# ArduinoCustomSchematic.net
KiCad netlist of a schematic drawn in Altium Designer
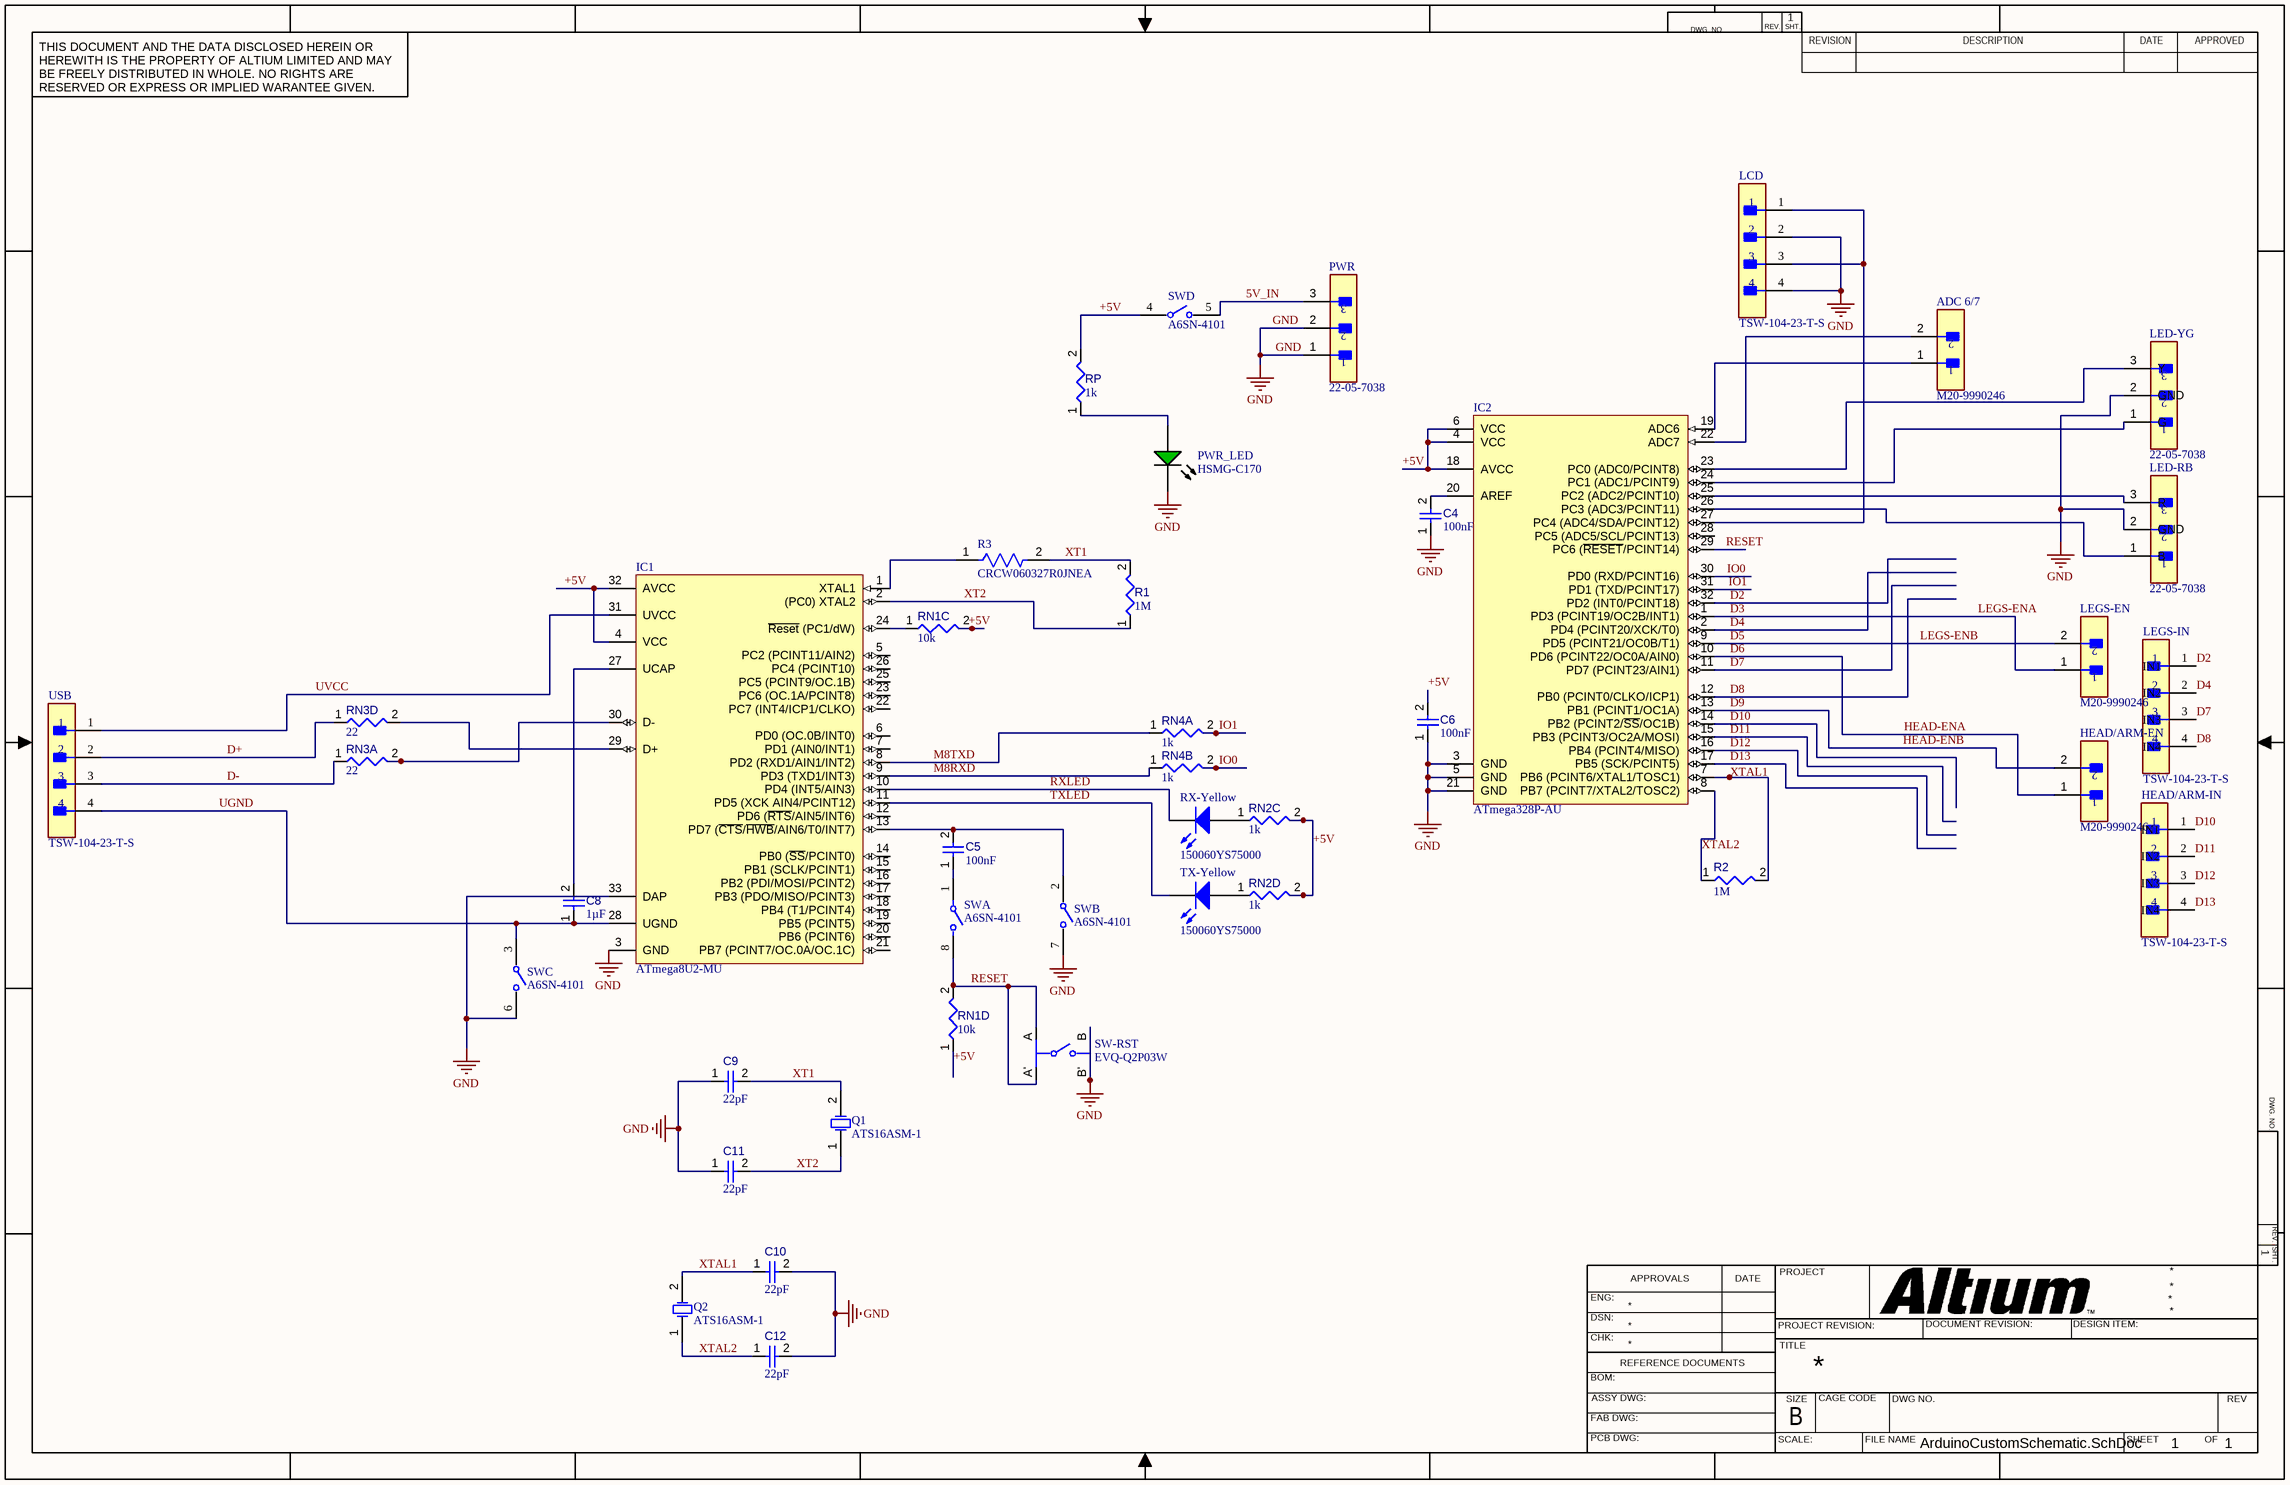
[diagram p0: ArduinoCustomSchematic.SchDoc]

(export (version "E")
  (design (tool "Eeschema 10.0.6"))
  (components
    (comp (ref "ADC 6/7")
      (value "M20-9990246")
      (footprint "FP-M20-9990246-MFG")
      (description "CONN HEADER VERT 2POS 2.54MM")
      (fields
        (field (name "OCTOPART") "https://octopart.com/m20-9990246-harwin-2590635")
        (field (name "MANUFACTURER") "Harwin")
      )
      (libsource (lib "Altium Content Vault") (part "3bc925449376181038e59eaffc5286c"))
    )
    (comp (ref "C4")
      (value "100nF")
      (footprint "CAPC2013X95X50LL10T25")
      (description "Chip Capacitor, 100 nF, +/- 10%, 50 V, 0805 (2012 Metric)")
      (fields (field (name "TOLERANCE") "10%") (field (name "Comment") "Capacitor 100 nF +/-10% 50 V 0805"))
      (libsource (lib "MY-PC-ER") (part "CAP-NP-2"))
    )
    (comp (ref "C5")
      (value "100nF")
      (footprint "CAPC2013X95X50LL10T25")
      (description "Chip Capacitor, 100 nF, +/- 10%, 50 V, 0805 (2012 Metric)")
      (fields (field (name "TOLERANCE") "10%") (field (name "Comment") "Capacitor 100 nF +/-10% 50 V 0805"))
      (libsource (lib "MY-PC-ER") (part "CAP-NP-2"))
    )
    (comp (ref "C6")
      (value "100nF")
      (footprint "CAPC2013X95X50LL10T25")
      (description "Chip Capacitor, 100 nF, +/- 10%, 50 V, 0805 (2012 Metric)")
      (fields (field (name "TOLERANCE") "10%") (field (name "Comment") "Capacitor 100 nF +/-10% 50 V 0805"))
      (libsource (lib "MY-PC-ER") (part "CAP-NP-2"))
    )
    (comp (ref "C8")
      (value "1µF")
      (footprint "CAPC1608X90X35ML15T15")
      (description "Chip Capacitor, 1 uF, +/- 10%, 16 V, 0603 (1608 Metric)")
      (fields (field (name "TOLERANCE") "10%") (field (name "Comment") "Capacitor 1uF +/- 10% 16V 0603"))
      (libsource (lib "MY-PC-ER") (part "CAP-NP-2"))
    )
    (comp (ref "C9")
      (value "22pF")
      (footprint "CAPC0402(1005)60_L")
      (description "Chip Capacitor, 22pF +/-10%, 50V, 0402, Thickness 0.6 mm")
      (fields (field (name "TOLERANCE") "10%") (field (name "Comment") "Capacitor 22pF +/-10% 50V 0402"))
      (libsource (lib "MY-PC-ER") (part "CAP-NP-2"))
    )
    (comp (ref "C10")
      (value "22pF")
      (footprint "CAPC0402(1005)60_L")
      (description "Chip Capacitor, 22pF +/-10%, 50V, 0402, Thickness 0.6 mm")
      (fields (field (name "TOLERANCE") "10%") (field (name "Comment") "Capacitor 22pF +/-10% 50V 0402"))
      (libsource (lib "MY-PC-ER") (part "CAP-NP-2"))
    )
    (comp (ref "C11")
      (value "22pF")
      (footprint "CAPC0402(1005)60_L")
      (description "Chip Capacitor, 22pF +/-10%, 50V, 0402, Thickness 0.6 mm")
      (fields (field (name "TOLERANCE") "10%") (field (name "Comment") "Capacitor 22pF +/-10% 50V 0402"))
      (libsource (lib "MY-PC-ER") (part "CAP-NP-2"))
    )
    (comp (ref "C12")
      (value "22pF")
      (footprint "CAPC0402(1005)60_L")
      (description "Chip Capacitor, 22pF +/-10%, 50V, 0402, Thickness 0.6 mm")
      (fields (field (name "TOLERANCE") "10%") (field (name "Comment") "Capacitor 22pF +/-10% 50V 0402"))
      (libsource (lib "MY-PC-ER") (part "CAP-NP-2"))
    )
    (comp (ref "HEAD/ARM-EN")
      (value "M20-9990246")
      (footprint "FP-M20-9990246-MFG")
      (description "CONN HEADER VERT 2POS 2.54MM")
      (fields
        (field (name "OCTOPART") "https://octopart.com/m20-9990246-harwin-2590635")
        (field (name "MANUFACTURER") "Harwin")
      )
      (libsource (lib "Altium Content Vault") (part "3bc925449376181038e59eaffc5286c"))
    )
    (comp (ref "HEAD/ARM-IN")
      (value "TSW-104-23-T-S")
      (footprint "FP-TSW-104-23-T-S-MFG")
      (description "CONN HEADER VERT 4POS 2.54MM")
      (libsource (lib "Altium Content Vault") (part "f33e0d423099bbb9e64512431cdbdf7"))
    )
    (comp (ref "IC1")
      (value "ATmega8U2-MU")
      (footprint "32PG_M")
      (libsource (lib "Altium Content Vault") (part "MC-8B-ATM8U2-SQ33"))
    )
    (comp (ref "IC2")
      (value "ATmega328P-AU")
      (footprint "32A_M")
      (libsource (lib "Altium Content Vault") (part "MC-8B-ATM48-SQ32"))
    )
    (comp (ref "LCD")
      (value "TSW-104-23-T-S")
      (footprint "FP-TSW-104-23-T-S-MFG")
      (description "CONN HEADER VERT 4POS 2.54MM")
      (libsource (lib "") (part "f33e0d423099bbb9e64512431cdbdf7_1"))
    )
    (comp (ref "LED-RB")
      (value "22-05-7038")
      (footprint "FP-22-05-7038-MFG")
      (description "CONN HEADER R/A 3POS 2.54MM")
      (fields
        (field (name "OCTOPART") "https://octopart.com/22-05-7038-molex-773563")
        (field (name "MANUFACTURER") "Molex")
      )
      (libsource (lib "") (part "0d3f023dd272f625e17a2be33dea85f_1"))
    )
    (comp (ref "LED-YG")
      (value "22-05-7038")
      (footprint "FP-22-05-7038-MFG")
      (description "CONN HEADER R/A 3POS 2.54MM")
      (fields
        (field (name "OCTOPART") "https://octopart.com/22-05-7038-molex-773563")
        (field (name "MANUFACTURER") "Molex")
      )
      (libsource (lib "") (part "0d3f023dd272f625e17a2be33dea85f_2"))
    )
    (comp (ref "LEGS-EN")
      (value "M20-9990246")
      (footprint "FP-M20-9990246-MFG")
      (description "CONN HEADER VERT 2POS 2.54MM")
      (fields
        (field (name "OCTOPART") "https://octopart.com/m20-9990246-harwin-2590635")
        (field (name "MANUFACTURER") "Harwin")
      )
      (libsource (lib "Altium Content Vault") (part "3bc925449376181038e59eaffc5286c"))
    )
    (comp (ref "LEGS-IN")
      (value "TSW-104-23-T-S")
      (footprint "FP-TSW-104-23-T-S-MFG")
      (description "CONN HEADER VERT 4POS 2.54MM")
      (libsource (lib "Altium Content Vault") (part "f33e0d423099bbb9e64512431cdbdf7"))
    )
    (comp (ref "PWR")
      (value "22-05-7038")
      (footprint "FP-22-05-7038-MFG")
      (description "CONN HEADER R/A 3POS 2.54MM")
      (fields
        (field (name "OCTOPART") "https://octopart.com/22-05-7038-molex-773563")
        (field (name "MANUFACTURER") "Molex")
      )
      (libsource (lib "Altium Content Vault") (part "0d3f023dd272f625e17a2be33dea85f"))
    )
    (comp (ref "PWR_LED")
      (value "HSMG-C170")
      (footprint "AVAG-HSMX-C170_V")
      (description "Chip LED, Green, 2.2 V, -40 to 85 degC, 2-Pin SMD, Pb-Free, Tape and Reel")
      (fields (field (name "MANUFACTURER") "Avago"))
      (libsource (lib "Altium Content Vault") (part "LED_GREEN_A1K2-2"))
    )
    (comp (ref "Q1")
      (value "ATS16ASM-1")
      (footprint "CTS-ATS-SM-XTAL-2")
      (description "ATS-SM Series Quartz Crystal, 16 MHz, -20 to 70 degC, 11.1 x 4.83 x 4.3mm SMD, RoHS, Tape and Reel")
      (fields (field (name "MANUFACTURER") "CTS Corporation"))
      (libsource (lib "Altium Content Vault") (part "CTS-ATS-SM-XTAL-2"))
    )
    (comp (ref "Q2")
      (value "ATS16ASM-1")
      (footprint "CTS-ATS-SM-XTAL-2")
      (description "ATS-SM Series Quartz Crystal, 16 MHz, -20 to 70 degC, 11.1 x 4.83 x 4.3mm SMD, RoHS, Tape and Reel")
      (fields (field (name "MANUFACTURER") "CTS Corporation"))
      (libsource (lib "Altium Content Vault") (part "CTS-ATS-SM-XTAL-2"))
    )
    (comp (ref "R1")
      (value "1M")
      (footprint "RESC0402(1005)_L")
      (description "Chip Resistor, 1 MOhms, +/-5 %, 63 mW, -55 to 155 degC, 0402")
      (fields (field (name "POWER") "63mW") (field (name "TOLERANCE") "5%"))
      (libsource (lib "MY-PC-ER") (part "RES-2"))
    )
    (comp (ref "R2")
      (value "1M")
      (footprint "RESC0402(1005)_L")
      (description "Chip Resistor, 1 MOhms, +/-5 %, 63 mW, -55 to 155 degC, 0402")
      (fields (field (name "POWER") "63mW") (field (name "TOLERANCE") "5%"))
      (libsource (lib "MY-PC-ER") (part "RES-2"))
    )
    (comp (ref "R3")
      (value "CRCW060327R0JNEA")
      (footprint "FP-CRCW0603-e3-IPC_B")
      (description "RES Thick Film, 27Ω, 5%, 0.1W, 200ppm/°C, 0603")
      (fields (field (name "TOLERANCE") "5%"))
      (libsource (lib "Altium Content Vault") (part "1029c3af85768c4190bb7ad29bc67b5"))
    )
    (comp (ref "RN1C")
      (value "10k")
      (footprint "RESC0402(1005)_L")
      (description "Chip Resistor, 10 kOhms, +/-1 %, 63 mW, -55 to 125 degC, 0402")
      (fields (field (name "POWER") "63mW") (field (name "TOLERANCE") "1%"))
      (libsource (lib "MY-PC-ER") (part "RES-2"))
    )
    (comp (ref "RN1D")
      (value "10k")
      (footprint "RESC0402(1005)_L")
      (description "Chip Resistor, 10 kOhms, +/-1 %, 63 mW, -55 to 125 degC, 0402")
      (fields (field (name "POWER") "63mW") (field (name "TOLERANCE") "1%"))
      (libsource (lib "MY-PC-ER") (part "RES-2"))
    )
    (comp (ref "RN2C")
      (value "1k")
      (footprint "RESC0402(1005)_L")
      (description "Chip Resistor, 1 kOhms, +/-5 %, 63 mW, -55 to 155 degC, 0402")
      (fields (field (name "POWER") "63mW") (field (name "TOLERANCE") "5%"))
      (libsource (lib "MY-PC-ER") (part "RES-2"))
    )
    (comp (ref "RN2D")
      (value "1k")
      (footprint "RESC0402(1005)_L")
      (description "Chip Resistor, 1 kOhms, +/-5 %, 63 mW, -55 to 155 degC, 0402")
      (fields (field (name "POWER") "63mW") (field (name "TOLERANCE") "5%"))
      (libsource (lib "MY-PC-ER") (part "RES-2"))
    )
    (comp (ref "RN3A")
      (value "22")
      (footprint "RESC0402(1005)_L")
      (description "Chip Resistor, 22 Ohms, +/-5 %, 63 mW, -55 to 155 degC, 0402")
      (fields (field (name "TOLERANCE") "5%") (field (name "POWER") "63mW"))
      (libsource (lib "MY-PC-ER") (part "RES-2"))
    )
    (comp (ref "RN3D")
      (value "22")
      (footprint "RESC0402(1005)_L")
      (description "Chip Resistor, 22 Ohms, +/-5 %, 63 mW, -55 to 155 degC, 0402")
      (fields (field (name "TOLERANCE") "5%") (field (name "POWER") "63mW"))
      (libsource (lib "MY-PC-ER") (part "RES-2"))
    )
    (comp (ref "RN4A")
      (value "1k")
      (footprint "RESC0402(1005)_L")
      (description "Chip Resistor, 1 kOhms, +/-5 %, 63 mW, -55 to 155 degC, 0402")
      (fields (field (name "POWER") "63mW") (field (name "TOLERANCE") "5%"))
      (libsource (lib "MY-PC-ER") (part "RES-2"))
    )
    (comp (ref "RN4B")
      (value "1k")
      (footprint "RESC0402(1005)_L")
      (description "Chip Resistor, 1 kOhms, +/-5 %, 63 mW, -55 to 155 degC, 0402")
      (fields (field (name "POWER") "63mW") (field (name "TOLERANCE") "5%"))
      (libsource (lib "MY-PC-ER") (part "RES-2"))
    )
    (comp (ref "RP")
      (value "1k")
      (footprint "RESC0805(2012)_L")
      (description "Chip Resistor, 1 kOhms, +/-5%, 125 mW, -55 to 155 degC, 0805")
      (fields (field (name "TOLERANCE") "5%") (field (name "POWER") "125mW"))
      (libsource (lib "MY-PC-ER") (part "RES-2"))
    )
    (comp (ref "RX-Yellow")
      (value "150060YS75000")
      (footprint "0603_A")
      (description "SMD mono-color Chip LED, WL-SMCW, Yellow")
      (fields (field (name "MANUFACTURER") "Wuerth Elektronik"))
      (libsource (lib "Altium Content Vault") (part "WE-LED_K1A2-2"))
    )
    (comp (ref "SW")
      (value "A6SN-4101")
      (footprint "FP-A6SN-4101-MFG")
      (description "RESET-EN")
      (libsource (lib "Altium Content Vault") (part "3efd76fef6de25c549b18e73c4a40b0"))
    )
    (comp (ref "SW-RST")
      (value "EVQ-Q2P03W")
      (footprint "FP-EVQ-Q2P03W-MFG")
      (description "SWITCH TACTILE SPST-NO 0.02A 15V")
      (libsource (lib "Altium Content Vault") (part "9677229990528492022b31d4503349f"))
    )
    (comp (ref "TX-Yellow")
      (value "150060YS75000")
      (footprint "0603_A")
      (description "SMD mono-color Chip LED, WL-SMCW, Yellow")
      (fields (field (name "MANUFACTURER") "Wuerth Elektronik"))
      (libsource (lib "Altium Content Vault") (part "WE-LED_K1A2-2"))
    )
    (comp (ref "USB")
      (value "TSW-104-23-T-S")
      (footprint "FP-TSW-104-23-T-S-MFG")
      (description "CONN HEADER VERT 4POS 2.54MM")
      (libsource (lib "") (part "f33e0d423099bbb9e64512431cdbdf7_1"))
    )
  )
  (nets
    (net (code "1") (name "/+5V") (class "Default")
      (node (ref "C6") (pin "2") (pinfunction "2_2") (pintype "passive"))
      (node (ref "IC1") (pin "32") (pinfunction "AVCC_32") (pintype "power_in"))
      (node (ref "IC1") (pin "4") (pinfunction "VCC_4") (pintype "power_in"))
      (node (ref "IC2") (pin "18") (pinfunction "AVCC_18") (pintype "power_in"))
      (node (ref "IC2") (pin "4") (pinfunction "VCC_4") (pintype "power_in"))
      (node (ref "IC2") (pin "6") (pinfunction "VCC_6") (pintype "power_in"))
      (node (ref "RN1C") (pin "2") (pinfunction "2_2") (pintype "passive"))
      (node (ref "RN1D") (pin "1") (pinfunction "1_1") (pintype "passive"))
      (node (ref "RN2C") (pin "2") (pinfunction "2_2") (pintype "passive"))
      (node (ref "RN2D") (pin "2") (pinfunction "2_2") (pintype "passive"))
      (node (ref "RP") (pin "2") (pinfunction "2_2") (pintype "passive"))
      (node (ref "SW") (pin "4") (pinfunction "4_4") (pintype "passive"))
    )
    (net (code "2") (name "/5V_IN") (class "Default")
      (node (ref "PWR") (pin "3") (pinfunction "3_3") (pintype "passive"))
      (node (ref "SW") (pin "5") (pinfunction "5_5") (pintype "passive"))
    )
    (net (code "3") (name "/D+") (class "Default")
      (node (ref "RN3D") (pin "1") (pinfunction "1_1") (pintype "passive"))
      (node (ref "USB") (pin "2") (pinfunction "D+_2") (pintype "passive"))
    )
    (net (code "4") (name "/D-") (class "Default")
      (node (ref "RN3A") (pin "1") (pinfunction "1_1") (pintype "passive"))
      (node (ref "USB") (pin "3") (pinfunction "D-_3") (pintype "passive"))
    )
    (net (code "5") (name "/D2") (class "Default")
      (node (ref "IC2") (pin "32") (pinfunction "PD2_(INT0/PCINT18)_32") (pintype "bidirectional"))
      (node (ref "LEGS-IN") (pin "1") (pinfunction "IN1_1") (pintype "passive"))
    )
    (net (code "6") (name "/D3") (class "Default")
      (node (ref "IC2") (pin "1") (pinfunction "PD3_(PCINT19/OC2B/INT1)_1") (pintype "bidirectional"))
      (node (ref "LEGS-EN") (pin "1") (pinfunction "1_1") (pintype "passive"))
    )
    (net (code "7") (name "/D4") (class "Default")
      (node (ref "IC2") (pin "2") (pinfunction "PD4_(PCINT20/XCK/T0)_2") (pintype "bidirectional"))
      (node (ref "LEGS-IN") (pin "2") (pinfunction "IN2_2") (pintype "passive"))
    )
    (net (code "8") (name "/D5") (class "Default")
      (node (ref "IC2") (pin "9") (pinfunction "PD5_(PCINT21/OC0B/T1)_9") (pintype "bidirectional"))
      (node (ref "LEGS-EN") (pin "2") (pinfunction "2_2") (pintype "passive"))
    )
    (net (code "9") (name "/D6") (class "Default")
      (node (ref "HEAD/ARM-EN") (pin "1") (pinfunction "1_1") (pintype "passive"))
      (node (ref "IC2") (pin "10") (pinfunction "PD6_(PCINT22/OC0A/AIN0)_10") (pintype "bidirectional"))
    )
    (net (code "10") (name "/D7") (class "Default")
      (node (ref "IC2") (pin "11") (pinfunction "PD7_(PCINT23/AIN1)_11") (pintype "bidirectional"))
      (node (ref "LEGS-IN") (pin "3") (pinfunction "IN3_3") (pintype "passive"))
    )
    (net (code "11") (name "/D8") (class "Default")
      (node (ref "IC2") (pin "12") (pinfunction "PB0_(PCINT0/CLKO/ICP1)_12") (pintype "bidirectional"))
      (node (ref "LEGS-IN") (pin "4") (pinfunction "IN4_4") (pintype "passive"))
    )
    (net (code "12") (name "/D9") (class "Default")
      (node (ref "HEAD/ARM-EN") (pin "2") (pinfunction "2_2") (pintype "passive"))
      (node (ref "IC2") (pin "13") (pinfunction "PB1_(PCINT1/OC1A)_13") (pintype "bidirectional"))
    )
    (net (code "13") (name "/D10") (class "Default")
      (node (ref "HEAD/ARM-IN") (pin "1") (pinfunction "IN1_1") (pintype "passive"))
      (node (ref "IC2") (pin "14") (pinfunction "PB2_(PCINT2/~{SS}/OC1B)_14") (pintype "bidirectional"))
    )
    (net (code "14") (name "/D11") (class "Default")
      (node (ref "HEAD/ARM-IN") (pin "2") (pinfunction "IN2_2") (pintype "passive"))
      (node (ref "IC2") (pin "15") (pinfunction "PB3_(PCINT3/OC2A/MOSI)_15") (pintype "bidirectional"))
    )
    (net (code "15") (name "/D12") (class "Default")
      (node (ref "HEAD/ARM-IN") (pin "3") (pinfunction "IN3_3") (pintype "passive"))
      (node (ref "IC2") (pin "16") (pinfunction "PB4_(PCINT4/MISO)_16") (pintype "bidirectional"))
    )
    (net (code "16") (name "/D13") (class "Default")
      (node (ref "HEAD/ARM-IN") (pin "4") (pinfunction "IN4_4") (pintype "passive"))
      (node (ref "IC2") (pin "17") (pinfunction "PB5_(SCK/PCINT5)_17") (pintype "bidirectional"))
    )
    (net (code "17") (name "/IO0") (class "Default")
      (node (ref "IC2") (pin "30") (pinfunction "PD0_(RXD/PCINT16)_30") (pintype "bidirectional"))
      (node (ref "RN4B") (pin "2") (pinfunction "2_2") (pintype "passive"))
    )
    (net (code "18") (name "/IO1") (class "Default")
      (node (ref "IC2") (pin "31") (pinfunction "PD1_(TXD/PCINT17)_31") (pintype "bidirectional"))
      (node (ref "RN4A") (pin "2") (pinfunction "2_2") (pintype "passive"))
    )
    (net (code "19") (name "/M8RXD") (class "Default")
      (node (ref "IC1") (pin "9") (pinfunction "PD3_(TXD1/INT3)_9") (pintype "bidirectional"))
      (node (ref "RN4B") (pin "1") (pinfunction "1_1") (pintype "passive"))
    )
    (net (code "20") (name "/M8TXD") (class "Default")
      (node (ref "IC1") (pin "8") (pinfunction "PD2_(RXD1/AIN1/INT2)_8") (pintype "bidirectional"))
      (node (ref "RN4A") (pin "1") (pinfunction "1_1") (pintype "passive"))
    )
    (net (code "21") (name "/RESET") (class "Default")
      (node (ref "IC2") (pin "29") (pinfunction "PC6_(~{RESET}/PCINT14)_29") (pintype "bidirectional"))
      (node (ref "RN1D") (pin "2") (pinfunction "2_2") (pintype "passive"))
      (node (ref "SW") (pin "8") (pinfunction "8_8") (pintype "passive"))
      (node (ref "SW-RST") (pin "A") (pinfunction "A_A") (pintype "passive"))
      (node (ref "SW-RST") (pin "A'") (pinfunction "A'_A'") (pintype "passive"))
    )
    (net (code "22") (name "/RXLED") (class "Default")
      (node (ref "IC1") (pin "10") (pinfunction "PD4_(INT5/AIN3)_10") (pintype "bidirectional"))
      (node (ref "RX-Yellow") (pin "1") (pinfunction "K_1") (pintype "passive"))
    )
    (net (code "23") (name "/TXLED") (class "Default")
      (node (ref "IC1") (pin "11") (pinfunction "PD5_(XCK_AIN4/PCINT12)_11") (pintype "bidirectional"))
      (node (ref "TX-Yellow") (pin "1") (pinfunction "K_1") (pintype "passive"))
    )
    (net (code "24") (name "/UGND") (class "Default")
      (node (ref "C8") (pin "1") (pinfunction "1_1") (pintype "passive"))
      (node (ref "IC1") (pin "28") (pinfunction "UGND_28") (pintype "power_in"))
      (node (ref "SW") (pin "3") (pinfunction "3_3") (pintype "passive"))
      (node (ref "USB") (pin "4") (pinfunction "GND_4") (pintype "passive"))
    )
    (net (code "25") (name "/UVCC") (class "Default")
      (node (ref "IC1") (pin "31") (pinfunction "UVCC_31") (pintype "power_in"))
      (node (ref "USB") (pin "1") (pinfunction "UVCC_1") (pintype "passive"))
    )
    (net (code "26") (name "/XT1") (class "Default")
      (node (ref "C9") (pin "2") (pinfunction "2_2") (pintype "passive"))
      (node (ref "Q1") (pin "2") (pinfunction "X2_2") (pintype "passive"))
      (node (ref "R1") (pin "2") (pinfunction "2_2") (pintype "passive"))
      (node (ref "R3") (pin "2") (pinfunction "2_2") (pintype "passive"))
    )
    (net (code "27") (name "/XT2") (class "Default")
      (node (ref "C11") (pin "2") (pinfunction "2_2") (pintype "passive"))
      (node (ref "IC1") (pin "2") (pinfunction "(PC0)_XTAL2_2") (pintype "bidirectional"))
      (node (ref "Q1") (pin "1") (pinfunction "X1_1") (pintype "passive"))
      (node (ref "R1") (pin "1") (pinfunction "1_1") (pintype "passive"))
    )
    (net (code "28") (name "/XTAL1") (class "Default")
      (node (ref "C10") (pin "1") (pinfunction "1_1") (pintype "passive"))
      (node (ref "IC2") (pin "7") (pinfunction "PB6_(PCINT6/XTAL1/TOSC1)_7") (pintype "bidirectional"))
      (node (ref "Q2") (pin "2") (pinfunction "X2_2") (pintype "passive"))
      (node (ref "R2") (pin "2") (pinfunction "2_2") (pintype "passive"))
    )
    (net (code "29") (name "/XTAL2") (class "Default")
      (node (ref "C12") (pin "1") (pinfunction "1_1") (pintype "passive"))
      (node (ref "IC2") (pin "8") (pinfunction "PB7_(PCINT7/XTAL2/TOSC2)_8") (pintype "bidirectional"))
      (node (ref "Q2") (pin "1") (pinfunction "X1_1") (pintype "passive"))
      (node (ref "R2") (pin "1") (pinfunction "1_1") (pintype "passive"))
    )
    (net (code "30") (name "GND") (class "Default")
      (node (ref "C10") (pin "2") (pinfunction "2_2") (pintype "passive"))
      (node (ref "C11") (pin "1") (pinfunction "1_1") (pintype "passive"))
      (node (ref "C12") (pin "2") (pinfunction "2_2") (pintype "passive"))
      (node (ref "C4") (pin "1") (pinfunction "1_1") (pintype "passive"))
      (node (ref "C6") (pin "1") (pinfunction "1_1") (pintype "passive"))
      (node (ref "C9") (pin "1") (pinfunction "1_1") (pintype "passive"))
      (node (ref "IC1") (pin "3") (pinfunction "GND_3") (pintype "power_in"))
      (node (ref "IC1") (pin "33") (pinfunction "DAP_33") (pintype "power_in"))
      (node (ref "IC2") (pin "21") (pinfunction "GND_21") (pintype "power_in"))
      (node (ref "IC2") (pin "3") (pinfunction "GND_3") (pintype "power_in"))
      (node (ref "IC2") (pin "5") (pinfunction "GND_5") (pintype "power_in"))
      (node (ref "LCD") (pin "2") (pinfunction "D+_2") (pintype "passive"))
      (node (ref "LCD") (pin "4") (pinfunction "GND_4") (pintype "passive"))
      (node (ref "LED-RB") (pin "2") (pinfunction "GND_2") (pintype "passive"))
      (node (ref "LED-YG") (pin "2") (pinfunction "GND_2") (pintype "passive"))
      (node (ref "PWR") (pin "1") (pinfunction "1_1") (pintype "passive"))
      (node (ref "PWR") (pin "2") (pinfunction "2_2") (pintype "passive"))
      (node (ref "PWR_LED") (pin "2") (pinfunction "K_2") (pintype "passive"))
      (node (ref "SW") (pin "6") (pinfunction "6_6") (pintype "passive"))
      (node (ref "SW") (pin "7") (pinfunction "7_7") (pintype "passive"))
      (node (ref "SW-RST") (pin "B") (pinfunction "B_B") (pintype "passive"))
      (node (ref "SW-RST") (pin "B'") (pinfunction "B'_B'") (pintype "passive"))
    )
    (net (code "31") (name "Net-(C5-Pad1)") (class "Default")
      (node (ref "C5") (pin "1") (pinfunction "1_1") (pintype "passive"))
      (node (ref "SW") (pin "1") (pinfunction "1_1") (pintype "passive"))
    )
    (net (code "32") (name "Net-(IC1-D+)") (class "Default")
      (node (ref "IC1") (pin "29") (pinfunction "D+_29") (pintype "bidirectional"))
      (node (ref "RN3D") (pin "2") (pinfunction "2_2") (pintype "passive"))
    )
    (net (code "33") (name "Net-(IC1-D-)") (class "Default")
      (node (ref "IC1") (pin "30") (pinfunction "D-_30") (pintype "bidirectional"))
      (node (ref "RN3A") (pin "2") (pinfunction "2_2") (pintype "passive"))
    )
    (net (code "34") (name "Net-(IC1-PD7_(~{CTS}{slash}~{HWB}{slash}AIN6{slash}T0{slash}INT7))") (class "Default")
      (node (ref "C5") (pin "2") (pinfunction "2_2") (pintype "passive"))
      (node (ref "IC1") (pin "13") (pinfunction "PD7_(~{CTS}/~{HWB}/AIN6/T0/INT7)_13") (pintype "bidirectional"))
      (node (ref "SW") (pin "2") (pinfunction "2_2") (pintype "passive"))
    )
    (net (code "35") (name "Net-(IC1-UCAP)") (class "Default")
      (node (ref "C8") (pin "2") (pinfunction "2_2") (pintype "passive"))
      (node (ref "IC1") (pin "27") (pinfunction "UCAP_27") (pintype "power_in"))
    )
    (net (code "36") (name "Net-(IC1-XTAL1)") (class "Default")
      (node (ref "IC1") (pin "1") (pinfunction "XTAL1_1") (pintype "input"))
      (node (ref "R3") (pin "1") (pinfunction "1_1") (pintype "passive"))
    )
    (net (code "37") (name "Net-(IC1-~{Reset}_(PC1{slash}dW))") (class "Default")
      (node (ref "IC1") (pin "24") (pinfunction "~{Reset}_(PC1/dW)_24") (pintype "bidirectional"))
      (node (ref "RN1C") (pin "1") (pinfunction "1_1") (pintype "passive"))
    )
    (net (code "38") (name "Net-(IC2-ADC6)") (class "Default")
      (node (ref "ADC 6/7") (pin "1") (pinfunction "1_1") (pintype "passive"))
      (node (ref "IC2") (pin "19") (pinfunction "ADC6_19") (pintype "input"))
    )
    (net (code "39") (name "Net-(IC2-ADC7)") (class "Default")
      (node (ref "ADC 6/7") (pin "2") (pinfunction "2_2") (pintype "passive"))
      (node (ref "IC2") (pin "22") (pinfunction "ADC7_22") (pintype "input"))
    )
    (net (code "40") (name "Net-(IC2-AREF)") (class "Default")
      (node (ref "C4") (pin "2") (pinfunction "2_2") (pintype "passive"))
      (node (ref "IC2") (pin "20") (pinfunction "AREF_20") (pintype "passive"))
    )
    (net (code "41") (name "Net-(IC2-PC0_(ADC0{slash}PCINT8))") (class "Default")
      (node (ref "IC2") (pin "23") (pinfunction "PC0_(ADC0/PCINT8)_23") (pintype "bidirectional"))
      (node (ref "LED-YG") (pin "3") (pinfunction "Y_3") (pintype "passive"))
    )
    (net (code "42") (name "Net-(IC2-PC1_(ADC1{slash}PCINT9))") (class "Default")
      (node (ref "IC2") (pin "24") (pinfunction "PC1_(ADC1/PCINT9)_24") (pintype "bidirectional"))
      (node (ref "LED-YG") (pin "1") (pinfunction "G_1") (pintype "passive"))
    )
    (net (code "43") (name "Net-(IC2-PC2_(ADC2{slash}PCINT10))") (class "Default")
      (node (ref "IC2") (pin "25") (pinfunction "PC2_(ADC2/PCINT10)_25") (pintype "bidirectional"))
      (node (ref "LED-RB") (pin "3") (pinfunction "R_3") (pintype "passive"))
    )
    (net (code "44") (name "Net-(IC2-PC3_(ADC3{slash}PCINT11))") (class "Default")
      (node (ref "IC2") (pin "26") (pinfunction "PC3_(ADC3/PCINT11)_26") (pintype "bidirectional"))
      (node (ref "LED-RB") (pin "1") (pinfunction "B_1") (pintype "passive"))
    )
    (net (code "45") (name "Net-(IC2-PC4_(ADC4{slash}SDA{slash}PCINT12))") (class "Default")
      (node (ref "IC2") (pin "27") (pinfunction "PC4_(ADC4/SDA/PCINT12)_27") (pintype "bidirectional"))
      (node (ref "LCD") (pin "1") (pinfunction "UVCC_1") (pintype "passive"))
      (node (ref "LCD") (pin "3") (pinfunction "D-_3") (pintype "passive"))
    )
    (net (code "46") (name "Net-(PWR_LED-A)") (class "Default")
      (node (ref "PWR_LED") (pin "1") (pinfunction "A_1") (pintype "passive"))
      (node (ref "RP") (pin "1") (pinfunction "1_1") (pintype "passive"))
    )
    (net (code "47") (name "Net-(RX-Yellow-A)") (class "Default")
      (node (ref "RN2C") (pin "1") (pinfunction "1_1") (pintype "passive"))
      (node (ref "RX-Yellow") (pin "2") (pinfunction "A_2") (pintype "passive"))
    )
    (net (code "48") (name "Net-(TX-Yellow-A)") (class "Default")
      (node (ref "RN2D") (pin "1") (pinfunction "1_1") (pintype "passive"))
      (node (ref "TX-Yellow") (pin "2") (pinfunction "A_2") (pintype "passive"))
    )
    (net (code "49") (name "unconnected-(IC1-PB0_(~{SS}{slash}PCINT0)-Pad14)") (class "Default")
      (node (ref "IC1") (pin "14") (pinfunction "PB0_(~{SS}/PCINT0)_14") (pintype "bidirectional"))
    )
    (net (code "50") (name "unconnected-(IC1-PB1_(SCLK{slash}PCINT1)-Pad15)") (class "Default")
      (node (ref "IC1") (pin "15") (pinfunction "PB1_(SCLK/PCINT1)_15") (pintype "bidirectional"))
    )
    (net (code "51") (name "unconnected-(IC1-PB2_(PDI{slash}MOSI{slash}PCINT2)-Pad16)") (class "Default")
      (node (ref "IC1") (pin "16") (pinfunction "PB2_(PDI/MOSI/PCINT2)_16") (pintype "bidirectional"))
    )
    (net (code "52") (name "unconnected-(IC1-PB3_(PDO{slash}MISO{slash}PCINT3)-Pad17)") (class "Default")
      (node (ref "IC1") (pin "17") (pinfunction "PB3_(PDO/MISO/PCINT3)_17") (pintype "bidirectional"))
    )
    (net (code "53") (name "unconnected-(IC1-PB4_(T1{slash}PCINT4)-Pad18)") (class "Default")
      (node (ref "IC1") (pin "18") (pinfunction "PB4_(T1/PCINT4)_18") (pintype "bidirectional"))
    )
    (net (code "54") (name "unconnected-(IC1-PB5_(PCINT5)-Pad19)") (class "Default")
      (node (ref "IC1") (pin "19") (pinfunction "PB5_(PCINT5)_19") (pintype "bidirectional"))
    )
    (net (code "55") (name "unconnected-(IC1-PB6_(PCINT6)-Pad20)") (class "Default")
      (node (ref "IC1") (pin "20") (pinfunction "PB6_(PCINT6)_20") (pintype "bidirectional"))
    )
    (net (code "56") (name "unconnected-(IC1-PB7_(PCINT7{slash}OC.0A{slash}OC.1C)-Pad21)") (class "Default")
      (node (ref "IC1") (pin "21") (pinfunction "PB7_(PCINT7/OC.0A/OC.1C)_21") (pintype "bidirectional"))
    )
    (net (code "57") (name "unconnected-(IC1-PC2_(PCINT11{slash}AIN2)-Pad5)") (class "Default")
      (node (ref "IC1") (pin "5") (pinfunction "PC2_(PCINT11/AIN2)_5") (pintype "bidirectional"))
    )
    (net (code "58") (name "unconnected-(IC1-PC4_(PCINT10)-Pad26)") (class "Default")
      (node (ref "IC1") (pin "26") (pinfunction "PC4_(PCINT10)_26") (pintype "bidirectional"))
    )
    (net (code "59") (name "unconnected-(IC1-PC5_(PCINT9{slash}OC.1B)-Pad25)") (class "Default")
      (node (ref "IC1") (pin "25") (pinfunction "PC5_(PCINT9/OC.1B)_25") (pintype "bidirectional"))
    )
    (net (code "60") (name "unconnected-(IC1-PC6_(OC.1A{slash}PCINT8)-Pad23)") (class "Default")
      (node (ref "IC1") (pin "23") (pinfunction "PC6_(OC.1A/PCINT8)_23") (pintype "bidirectional"))
    )
    (net (code "61") (name "unconnected-(IC1-PC7_(INT4{slash}ICP1{slash}CLKO)-Pad22)") (class "Default")
      (node (ref "IC1") (pin "22") (pinfunction "PC7_(INT4/ICP1/CLKO)_22") (pintype "bidirectional"))
    )
    (net (code "62") (name "unconnected-(IC1-PD0_(OC.0B{slash}INT0)-Pad6)") (class "Default")
      (node (ref "IC1") (pin "6") (pinfunction "PD0_(OC.0B/INT0)_6") (pintype "bidirectional"))
    )
    (net (code "63") (name "unconnected-(IC1-PD1_(AIN0{slash}INT1)-Pad7)") (class "Default")
      (node (ref "IC1") (pin "7") (pinfunction "PD1_(AIN0/INT1)_7") (pintype "bidirectional"))
    )
    (net (code "64") (name "unconnected-(IC1-PD6_(~{RTS}{slash}AIN5{slash}INT6)-Pad12)") (class "Default")
      (node (ref "IC1") (pin "12") (pinfunction "PD6_(~{RTS}/AIN5/INT6)_12") (pintype "bidirectional"))
    )
    (net (code "65") (name "unconnected-(IC2-PC5_(ADC5{slash}SCL{slash}PCINT13)-Pad28)") (class "Default")
      (node (ref "IC2") (pin "28") (pinfunction "PC5_(ADC5/SCL/PCINT13)_28") (pintype "bidirectional"))
    )
  )
)
